# OLED_BREAKOUT_SCH.net
KiCad netlist of a schematic drawn in Altium Designer
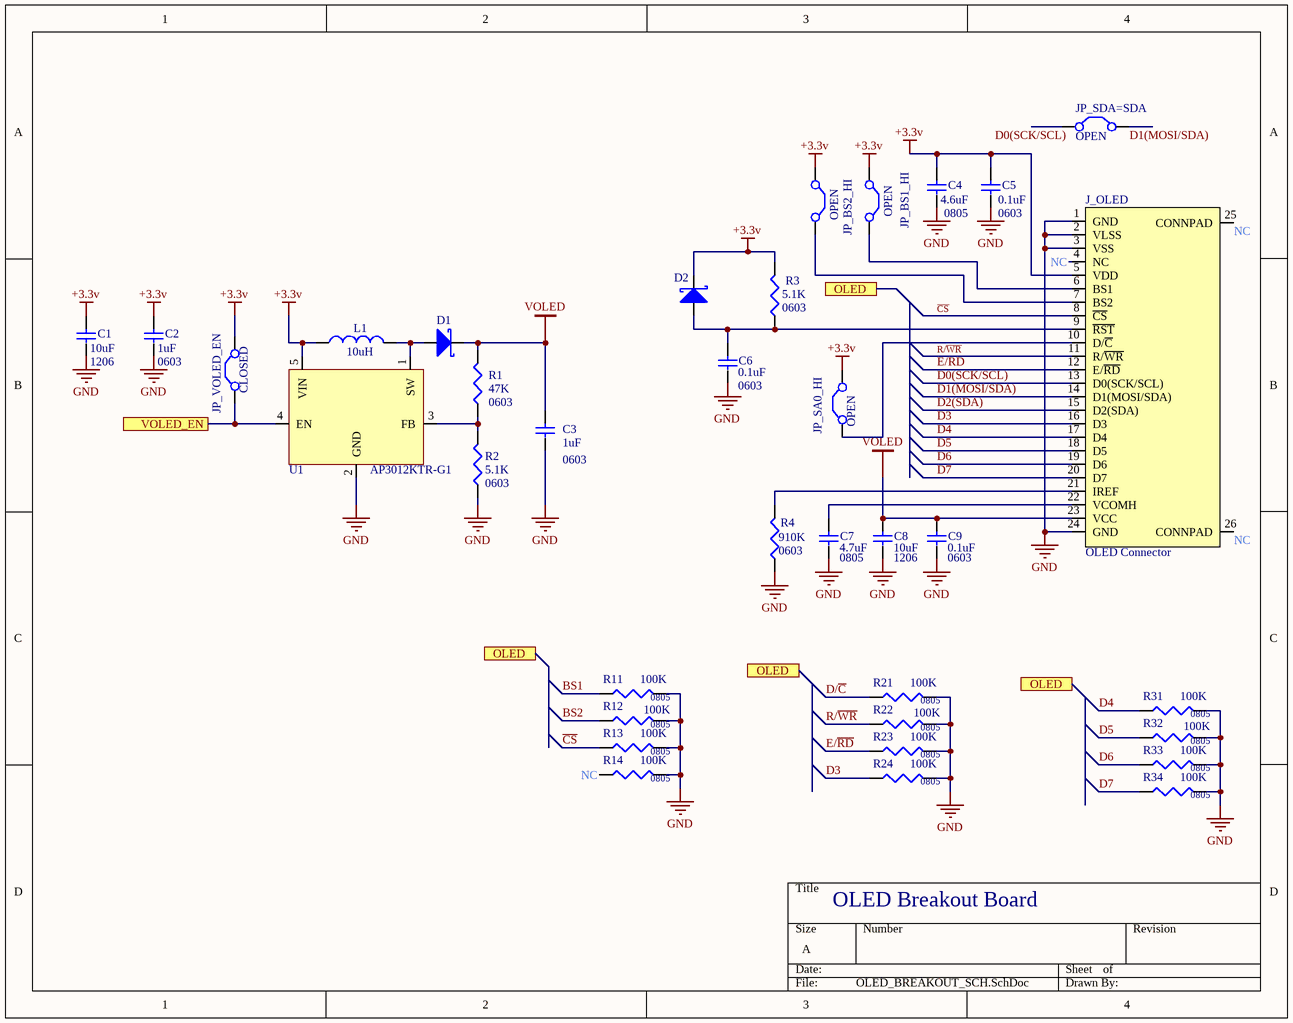
[diagram p0: OLED_BREAKOUT_SCH.SchDoc]

(export (version "E")
  (design (tool "Eeschema 10.0.6"))
  (components
    (comp (ref "C1")
      (value "Capacitor")
      (footprint "SMD-1206")
      (fields (field (name "CAPACTIANCE") "10uF") (field (name "SIZE") "1206"))
      (libsource (lib "OLED_BREAKOUT_SCH_LIB") (part "Capacitor"))
    )
    (comp (ref "C2")
      (value "Capacitor")
      (footprint "SMD-0603")
      (fields (field (name "CAPACITANCE") "1uF") (field (name "SIZE") "0603"))
      (libsource (lib "OLED_BREAKOUT_SCH_LIB") (part "Capacitor"))
    )
    (comp (ref "C3")
      (value "Capacitor")
      (footprint "SMD-0603")
      (fields (field (name "CAPACITANCE") "1uF") (field (name "SIZE") "0603"))
      (libsource (lib "OLED_BREAKOUT_SCH_LIB") (part "Capacitor"))
    )
    (comp (ref "C4")
      (value "Capacitor")
      (footprint "SMD-0805")
      (fields (field (name "CAPACITANCE") "4.6uF") (field (name "SIZE") "0805"))
      (libsource (lib "OLED_BREAKOUT_SCH_LIB") (part "Capacitor"))
    )
    (comp (ref "C5")
      (value "Capacitor")
      (footprint "SMD-0603")
      (fields (field (name "CAPACITANCE") "0.1uF") (field (name "SIZE") "0603"))
      (libsource (lib "OLED_BREAKOUT_SCH_LIB") (part "Capacitor"))
    )
    (comp (ref "C6")
      (value "Capacitor")
      (footprint "SMD-0603")
      (fields (field (name "CAPACITANCE") "0.1uF") (field (name "SIZE") "0603"))
      (libsource (lib "OLED_BREAKOUT_SCH_LIB") (part "Capacitor"))
    )
    (comp (ref "C7")
      (value "Capacitor")
      (footprint "SMD-0805")
      (fields (field (name "CAPACITANCE") "4.7uF") (field (name "SIZE") "0805"))
      (libsource (lib "OLED_BREAKOUT_SCH_LIB") (part "Capacitor"))
    )
    (comp (ref "C8")
      (value "Capacitor")
      (footprint "SMD-1206")
      (fields (field (name "CAPACITANCE") "10uF") (field (name "SIZE") "1206"))
      (libsource (lib "OLED_BREAKOUT_SCH_LIB") (part "Capacitor"))
    )
    (comp (ref "C9")
      (value "Capacitor")
      (footprint "SMD-0603")
      (fields (field (name "CAPACITANCE") "0.1uF") (field (name "SIZE") "0603"))
      (libsource (lib "OLED_BREAKOUT_SCH_LIB") (part "Capacitor"))
    )
    (comp (ref "D1")
      (value "Diode Schottky")
      (footprint "D1_SOD-123")
      (libsource (lib "OLED_BREAKOUT_SCH_LIB") (part "Diode Schottky"))
    )
    (comp (ref "D2")
      (value "Diode Schottky")
      (footprint "D2_SOD523")
      (libsource (lib "OLED_BREAKOUT_SCH_LIB") (part "Diode Schottky"))
    )
    (comp (ref "JP_BS1_HI")
      (value "Jumper")
      (footprint "SMD-0805")
      (description "Jumper Wire")
      (fields (field (name "STATE") "OPEN") (field (name "PUBLISHER") "Altium Limited"))
      (libsource (lib "Miscellaneous Devices") (part "Jumper"))
    )
    (comp (ref "JP_BS2_HI")
      (value "Jumper")
      (footprint "SMD-0805")
      (description "Jumper Wire")
      (fields (field (name "STATE") "OPEN") (field (name "PUBLISHER") "Altium Limited"))
      (libsource (lib "Miscellaneous Devices") (part "Jumper"))
    )
    (comp (ref "JP_SA0_HI")
      (value "Jumper")
      (footprint "SMD-0805")
      (description "Jumper Wire")
      (fields (field (name "STATE") "OPEN") (field (name "PUBLISHER") "Altium Limited"))
      (libsource (lib "Miscellaneous Devices") (part "Jumper"))
    )
    (comp (ref "JP_SDA=SDA")
      (value "Jumper")
      (footprint "SMD-0805")
      (description "Jumper Wire")
      (fields (field (name "STATE") "OPEN") (field (name "PUBLISHER") "Altium Limited"))
      (libsource (lib "Miscellaneous Devices") (part "Jumper"))
    )
    (comp (ref "JP_VOLED_EN")
      (value "Jumper")
      (footprint "SMD-0805")
      (description "Jumper Wire")
      (fields (field (name "STATE") "CLOSED") (field (name "PUBLISHER") "Altium Limited"))
      (libsource (lib "Miscellaneous Devices") (part "Jumper"))
    )
    (comp (ref "J_OLED")
      (value "OLED Connector")
      (footprint "J_OLED")
      (description "24 Position, 0.5mm Pitch, Gold, FCC FPC ZIF Connector")
      (libsource (lib "OLED_BREAKOUT_SCH_LIB") (part "OLED Connector"))
    )
    (comp (ref "L1")
      (value "Inductor")
      (fields (field (name "INDUCTANCE") "10uH"))
      (libsource (lib "OLED_BREAKOUT_SCH_LIB") (part "Inductor"))
    )
    (comp (ref "R1")
      (value "Resistor")
      (footprint "SMD-0603")
      (fields (field (name "RESISTANCE") "47K") (field (name "SIZE") "0603"))
      (libsource (lib "OLED_BREAKOUT_SCH_LIB") (part "Resistor"))
    )
    (comp (ref "R2")
      (value "Resistor")
      (footprint "SMD-0603")
      (fields (field (name "RESISTANCE") "5.1K") (field (name "SIZE") "0603"))
      (libsource (lib "OLED_BREAKOUT_SCH_LIB") (part "Resistor"))
    )
    (comp (ref "R3")
      (value "Resistor")
      (footprint "SMD-0603")
      (fields (field (name "RESISTANCE") "5.1K") (field (name "SIZE") "0603"))
      (libsource (lib "OLED_BREAKOUT_SCH_LIB") (part "Resistor"))
    )
    (comp (ref "R4")
      (value "Resistor")
      (footprint "SMD-0603")
      (fields (field (name "RESISTANCE") "910K") (field (name "SIZE") "0603"))
      (libsource (lib "OLED_BREAKOUT_SCH_LIB") (part "Resistor"))
    )
    (comp (ref "R11")
      (value "Resistor")
      (footprint "SMD-0805")
      (fields (field (name "RESISTANCE") "100K") (field (name "SIZE") "0805"))
      (libsource (lib "OLED_BREAKOUT_SCH_LIB") (part "Resistor"))
    )
    (comp (ref "R12")
      (value "Resistor")
      (footprint "SMD-0805")
      (fields (field (name "RESISTANCE") "100K") (field (name "SIZE") "0805"))
      (libsource (lib "OLED_BREAKOUT_SCH_LIB") (part "Resistor"))
    )
    (comp (ref "R13")
      (value "Resistor")
      (footprint "SMD-0805")
      (fields (field (name "RESISTANCE") "100K") (field (name "SIZE") "0805"))
      (libsource (lib "OLED_BREAKOUT_SCH_LIB") (part "Resistor"))
    )
    (comp (ref "R14")
      (value "Resistor")
      (footprint "SMD-0805")
      (fields (field (name "RESISTANCE") "100K") (field (name "SIZE") "0805"))
      (libsource (lib "OLED_BREAKOUT_SCH_LIB") (part "Resistor"))
    )
    (comp (ref "R21")
      (value "Resistor")
      (footprint "SMD-0805")
      (fields (field (name "RESISTANCE") "100K") (field (name "SIZE") "0805"))
      (libsource (lib "OLED_BREAKOUT_SCH_LIB") (part "Resistor"))
    )
    (comp (ref "R22")
      (value "Resistor")
      (footprint "SMD-0805")
      (fields (field (name "RESISTANCE") "100K") (field (name "SIZE") "0805"))
      (libsource (lib "OLED_BREAKOUT_SCH_LIB") (part "Resistor"))
    )
    (comp (ref "R23")
      (value "Resistor")
      (footprint "SMD-0805")
      (fields (field (name "RESISTANCE") "100K") (field (name "SIZE") "0805"))
      (libsource (lib "OLED_BREAKOUT_SCH_LIB") (part "Resistor"))
    )
    (comp (ref "R24")
      (value "Resistor")
      (footprint "SMD-0805")
      (fields (field (name "RESISTANCE") "100K") (field (name "SIZE") "0805"))
      (libsource (lib "OLED_BREAKOUT_SCH_LIB") (part "Resistor"))
    )
    (comp (ref "R31")
      (value "Resistor")
      (footprint "SMD-0805")
      (fields (field (name "RESISTANCE") "100K") (field (name "SIZE") "0805"))
      (libsource (lib "OLED_BREAKOUT_SCH_LIB") (part "Resistor"))
    )
    (comp (ref "R32")
      (value "Resistor")
      (footprint "SMD-0805")
      (fields (field (name "RESISTANCE") "100K") (field (name "SIZE") "0805"))
      (libsource (lib "OLED_BREAKOUT_SCH_LIB") (part "Resistor"))
    )
    (comp (ref "R33")
      (value "Resistor")
      (footprint "SMD-0805")
      (fields (field (name "RESISTANCE") "100K") (field (name "SIZE") "0805"))
      (libsource (lib "OLED_BREAKOUT_SCH_LIB") (part "Resistor"))
    )
    (comp (ref "R34")
      (value "Resistor")
      (footprint "SMD-0805")
      (fields (field (name "RESISTANCE") "100K") (field (name "SIZE") "0805"))
      (libsource (lib "OLED_BREAKOUT_SCH_LIB") (part "Resistor"))
    )
    (comp (ref "U1")
      (value "DC/DC Voltage Regulator")
      (footprint "U1_SOT-23-5")
      (description "Integrated Circuits (ICs)\nPMIC - Voltage Regulators - DC DC Switching Regulators")
      (fields (field (name "PART#") "AP3012KTR-G1"))
      (libsource (lib "OLED_BREAKOUT_SCH_LIB") (part "DC/DC Voltage Regulator"))
    )
  )
  (nets
    (net (code "1") (name "+3.3v") (class "Default")
      (node (ref "C1") (pin "2") (pinfunction "2_2") (pintype "passive"))
      (node (ref "C2") (pin "2") (pinfunction "2_2") (pintype "passive"))
      (node (ref "C4") (pin "2") (pinfunction "2_2") (pintype "passive"))
      (node (ref "C5") (pin "2") (pinfunction "2_2") (pintype "passive"))
      (node (ref "D2") (pin "2") (pinfunction "2_2") (pintype "passive"))
      (node (ref "JP_BS1_HI") (pin "1") (pinfunction "C1_1") (pintype "passive"))
      (node (ref "JP_BS2_HI") (pin "1") (pinfunction "C1_1") (pintype "passive"))
      (node (ref "JP_SA0_HI") (pin "2") (pinfunction "C2_2") (pintype "passive"))
      (node (ref "JP_VOLED_EN") (pin "2") (pinfunction "C2_2") (pintype "passive"))
      (node (ref "J_OLED") (pin "5") (pinfunction "VDD_5") (pintype "passive"))
      (node (ref "L1") (pin "1") (pinfunction "1_1") (pintype "passive"))
      (node (ref "R3") (pin "2") (pinfunction "2_2") (pintype "passive"))
      (node (ref "U1") (pin "5") (pinfunction "VIN_5") (pintype "passive"))
    )
    (net (code "2") (name "/BS1") (class "Default")
      (node (ref "R11") (pin "1") (pinfunction "1_1") (pintype "passive"))
    )
    (net (code "3") (name "/BS2") (class "Default")
      (node (ref "R12") (pin "1") (pinfunction "1_1") (pintype "passive"))
    )
    (net (code "4") (name "/D0(SCK{slash}SCL)") (class "Default")
      (node (ref "JP_SDA=SDA") (pin "1") (pinfunction "C1_1") (pintype "passive"))
      (node (ref "J_OLED") (pin "13") (pinfunction "D0(SCK/SCL)_13") (pintype "passive"))
    )
    (net (code "5") (name "/D1(MOSI{slash}SDA)") (class "Default")
      (node (ref "JP_SDA=SDA") (pin "2") (pinfunction "C2_2") (pintype "passive"))
      (node (ref "J_OLED") (pin "14") (pinfunction "D1(MOSI/SDA)_14") (pintype "passive"))
    )
    (net (code "6") (name "/D2(SDA)") (class "Default")
      (node (ref "J_OLED") (pin "15") (pinfunction "D2(SDA)_15") (pintype "passive"))
    )
    (net (code "7") (name "/D3") (class "Default")
      (node (ref "J_OLED") (pin "16") (pinfunction "D3_16") (pintype "passive"))
      (node (ref "R24") (pin "1") (pinfunction "1_1") (pintype "passive"))
    )
    (net (code "8") (name "/D4") (class "Default")
      (node (ref "J_OLED") (pin "17") (pinfunction "D4_17") (pintype "passive"))
      (node (ref "R31") (pin "1") (pinfunction "1_1") (pintype "passive"))
    )
    (net (code "9") (name "/D5") (class "Default")
      (node (ref "J_OLED") (pin "18") (pinfunction "D5_18") (pintype "passive"))
      (node (ref "R32") (pin "1") (pinfunction "1_1") (pintype "passive"))
    )
    (net (code "10") (name "/D6") (class "Default")
      (node (ref "J_OLED") (pin "19") (pinfunction "D6_19") (pintype "passive"))
      (node (ref "R33") (pin "1") (pinfunction "1_1") (pintype "passive"))
    )
    (net (code "11") (name "/D7") (class "Default")
      (node (ref "J_OLED") (pin "20") (pinfunction "D7_20") (pintype "passive"))
      (node (ref "R34") (pin "1") (pinfunction "1_1") (pintype "passive"))
    )
    (net (code "12") (name "/D{slash}~{C}") (class "Default")
      (node (ref "R21") (pin "1") (pinfunction "1_1") (pintype "passive"))
    )
    (net (code "13") (name "/E{slash}~{RD}") (class "Default")
      (node (ref "J_OLED") (pin "12") (pinfunction "E/~{RD}_12") (pintype "passive"))
      (node (ref "R23") (pin "1") (pinfunction "1_1") (pintype "passive"))
    )
    (net (code "14") (name "/NC") (class "Default")
      (node (ref "J_OLED") (pin "25") (pinfunction "CONNPAD_25") (pintype "passive"))
      (node (ref "J_OLED") (pin "26") (pinfunction "CONNPAD_26") (pintype "passive"))
      (node (ref "J_OLED") (pin "4") (pinfunction "NC_4") (pintype "passive"))
      (node (ref "R14") (pin "1") (pinfunction "1_1") (pintype "passive"))
    )
    (net (code "16") (name "/R{slash}~{WR}") (class "Default")
      (node (ref "J_OLED") (pin "11") (pinfunction "R/~{WR}_11") (pintype "passive"))
      (node (ref "R22") (pin "1") (pinfunction "1_1") (pintype "passive"))
    )
    (net (code "17") (name "/VOLED_EN") (class "Default")
      (node (ref "JP_VOLED_EN") (pin "1") (pinfunction "C1_1") (pintype "passive"))
      (node (ref "U1") (pin "4") (pinfunction "EN_4") (pintype "passive"))
    )
    (net (code "18") (name "/~{CS}") (class "Default")
      (node (ref "J_OLED") (pin "8") (pinfunction "~{CS}_8") (pintype "passive"))
      (node (ref "R13") (pin "1") (pinfunction "1_1") (pintype "passive"))
    )
    (net (code "19") (name "GND") (class "Default")
      (node (ref "C1") (pin "1") (pinfunction "1_1") (pintype "passive"))
      (node (ref "C2") (pin "1") (pinfunction "1_1") (pintype "passive"))
      (node (ref "C3") (pin "1") (pinfunction "1_1") (pintype "passive"))
      (node (ref "C4") (pin "1") (pinfunction "1_1") (pintype "passive"))
      (node (ref "C5") (pin "1") (pinfunction "1_1") (pintype "passive"))
      (node (ref "C6") (pin "1") (pinfunction "1_1") (pintype "passive"))
      (node (ref "C7") (pin "1") (pinfunction "1_1") (pintype "passive"))
      (node (ref "C8") (pin "1") (pinfunction "1_1") (pintype "passive"))
      (node (ref "C9") (pin "1") (pinfunction "1_1") (pintype "passive"))
      (node (ref "J_OLED") (pin "1") (pinfunction "GND_1") (pintype "passive"))
      (node (ref "J_OLED") (pin "2") (pinfunction "VLSS_2") (pintype "passive"))
      (node (ref "J_OLED") (pin "24") (pinfunction "GND_24") (pintype "passive"))
      (node (ref "J_OLED") (pin "3") (pinfunction "VSS_3") (pintype "passive"))
      (node (ref "R11") (pin "2") (pinfunction "2_2") (pintype "passive"))
      (node (ref "R12") (pin "2") (pinfunction "2_2") (pintype "passive"))
      (node (ref "R13") (pin "2") (pinfunction "2_2") (pintype "passive"))
      (node (ref "R14") (pin "2") (pinfunction "2_2") (pintype "passive"))
      (node (ref "R2") (pin "1") (pinfunction "1_1") (pintype "passive"))
      (node (ref "R21") (pin "2") (pinfunction "2_2") (pintype "passive"))
      (node (ref "R22") (pin "2") (pinfunction "2_2") (pintype "passive"))
      (node (ref "R23") (pin "2") (pinfunction "2_2") (pintype "passive"))
      (node (ref "R24") (pin "2") (pinfunction "2_2") (pintype "passive"))
      (node (ref "R31") (pin "2") (pinfunction "2_2") (pintype "passive"))
      (node (ref "R32") (pin "2") (pinfunction "2_2") (pintype "passive"))
      (node (ref "R33") (pin "2") (pinfunction "2_2") (pintype "passive"))
      (node (ref "R34") (pin "2") (pinfunction "2_2") (pintype "passive"))
      (node (ref "R4") (pin "1") (pinfunction "1_1") (pintype "passive"))
      (node (ref "U1") (pin "2") (pinfunction "GND_2") (pintype "passive"))
    )
    (net (code "20") (name "Net-(JP_BS1_HI-C2)") (class "Default")
      (node (ref "JP_BS1_HI") (pin "2") (pinfunction "C2_2") (pintype "passive"))
      (node (ref "J_OLED") (pin "6") (pinfunction "BS1_6") (pintype "passive"))
    )
    (net (code "21") (name "Net-(JP_BS2_HI-C2)") (class "Default")
      (node (ref "JP_BS2_HI") (pin "2") (pinfunction "C2_2") (pintype "passive"))
      (node (ref "J_OLED") (pin "7") (pinfunction "BS2_7") (pintype "passive"))
    )
    (net (code "22") (name "Net-(JP_SA0_HI-C1)") (class "Default")
      (node (ref "JP_SA0_HI") (pin "1") (pinfunction "C1_1") (pintype "passive"))
      (node (ref "J_OLED") (pin "10") (pinfunction "D/~{C}_10") (pintype "passive"))
    )
    (net (code "23") (name "Net-(J_OLED-IREF)") (class "Default")
      (node (ref "J_OLED") (pin "21") (pinfunction "IREF_21") (pintype "passive"))
      (node (ref "R4") (pin "2") (pinfunction "2_2") (pintype "passive"))
    )
    (net (code "24") (name "Net-(J_OLED-VCOMH)") (class "Default")
      (node (ref "C7") (pin "2") (pinfunction "2_2") (pintype "passive"))
      (node (ref "J_OLED") (pin "22") (pinfunction "VCOMH_22") (pintype "passive"))
    )
    (net (code "25") (name "Net-(J_OLED-~{RST})") (class "Default")
      (node (ref "C6") (pin "2") (pinfunction "2_2") (pintype "passive"))
      (node (ref "D2") (pin "1") (pinfunction "1_1") (pintype "passive"))
      (node (ref "J_OLED") (pin "9") (pinfunction "~{RST}_9") (pintype "passive"))
      (node (ref "R3") (pin "1") (pinfunction "1_1") (pintype "passive"))
    )
    (net (code "26") (name "Net-(U1-FB)") (class "Default")
      (node (ref "R1") (pin "1") (pinfunction "1_1") (pintype "passive"))
      (node (ref "R2") (pin "2") (pinfunction "2_2") (pintype "passive"))
      (node (ref "U1") (pin "3") (pinfunction "FB_3") (pintype "passive"))
    )
    (net (code "27") (name "Net-(U1-SW)") (class "Default")
      (node (ref "D1") (pin "1") (pinfunction "1_1") (pintype "passive"))
      (node (ref "L1") (pin "2") (pinfunction "2_2") (pintype "passive"))
      (node (ref "U1") (pin "1") (pinfunction "SW_1") (pintype "passive"))
    )
    (net (code "28") (name "VOLED") (class "Default")
      (node (ref "C3") (pin "2") (pinfunction "2_2") (pintype "passive"))
      (node (ref "C8") (pin "2") (pinfunction "2_2") (pintype "passive"))
      (node (ref "C9") (pin "2") (pinfunction "2_2") (pintype "passive"))
      (node (ref "D1") (pin "2") (pinfunction "2_2") (pintype "passive"))
      (node (ref "J_OLED") (pin "23") (pinfunction "VCC_23") (pintype "passive"))
      (node (ref "R1") (pin "2") (pinfunction "2_2") (pintype "passive"))
    )
  )
)
